# attiny84_bo.net
KiCad netlist of a schematic drawn in EAGLE
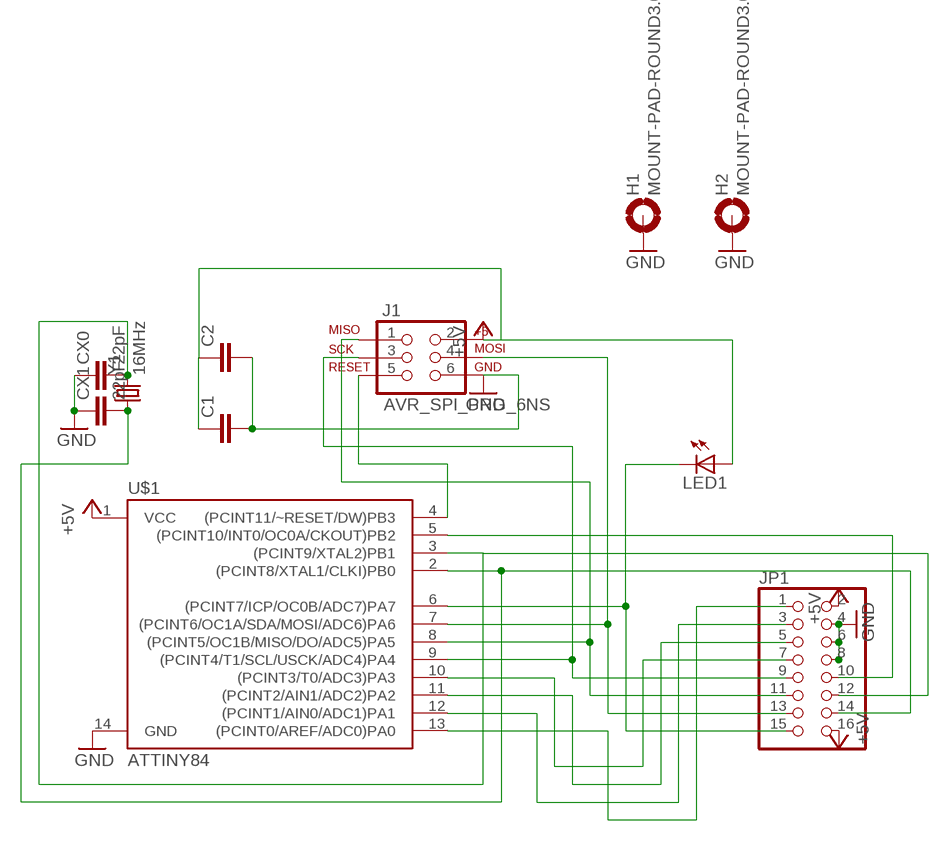
[diagram p0: schematic, sheet 1]

(export (version "E")
  (design (tool "Eeschema 10.0.6"))
  (components
    (comp (ref "C1")
      (value "C-EUC0805")
      (footprint "eagle-import:C0805")
      (libsource (lib "eagle-import") (part "C-EUC0805"))
    )
    (comp (ref "C2")
      (value "C-EUC0805")
      (footprint "eagle-import:C0805")
      (libsource (lib "eagle-import") (part "C-EUC0805"))
    )
    (comp (ref "CX0")
      (value "22pF")
      (footprint "eagle-import:C0603")
      (libsource (lib "eagle-import") (part "C-EUC0603"))
    )
    (comp (ref "CX1")
      (value "22pF")
      (footprint "eagle-import:C0603")
      (libsource (lib "eagle-import") (part "C-EUC0603"))
    )
    (comp (ref "H1")
      (value "MOUNT-PAD-ROUND3.0")
      (footprint "eagle-import:3,0-PAD")
      (libsource (lib "eagle-import") (part "MOUNT-PAD-ROUND3.0"))
    )
    (comp (ref "H2")
      (value "MOUNT-PAD-ROUND3.0")
      (footprint "eagle-import:3,0-PAD")
      (libsource (lib "eagle-import") (part "MOUNT-PAD-ROUND3.0"))
    )
    (comp (ref "J1")
      (value "AVR_SPI_PRG_6NS")
      (footprint "eagle-import:2X3-NS")
      (libsource (lib "eagle-import") (part "AVR_SPI_PRG_6NS"))
    )
    (comp (ref "JP1")
      (value "PINHD-2X8")
      (footprint "eagle-import:2X08")
      (libsource (lib "eagle-import") (part "PINHD-2X8"))
    )
    (comp (ref "LED1")
      (value "LED0603")
      (footprint "eagle-import:LED-0603")
      (libsource (lib "eagle-import") (part "LED0603"))
    )
    (comp (ref "U$1")
      (value "ATTINY84")
      (footprint "eagle-import:SO14")
      (libsource (lib "eagle-import") (part "ATTINY84"))
    )
    (comp (ref "Y1")
      (value "16MHz")
      (footprint "eagle-import:CRYSTAL-SMD-5X3")
      (libsource (lib "eagle-import") (part "CRYSTAL5X3"))
    )
  )
  (nets
    (net (code "1") (name "+5V") (class "Default")
      (node (ref "C1") (pin "1") (pinfunction "1_1") (pintype "passive"))
      (node (ref "C2") (pin "1") (pinfunction "1_1") (pintype "passive"))
      (node (ref "J1") (pin "2") (pinfunction "2_2") (pintype "passive"))
      (node (ref "JP1") (pin "16") (pinfunction "16_16") (pintype "passive"))
      (node (ref "JP1") (pin "2") (pinfunction "2_2") (pintype "passive"))
      (node (ref "LED1") (pin "A") (pinfunction "A_A") (pintype "passive"))
      (node (ref "U$1") (pin "1") (pinfunction "VCC_1") (pintype "bidirectional"))
    )
    (net (code "2") (name "GND") (class "Default")
      (node (ref "C1") (pin "2") (pinfunction "2_2") (pintype "passive"))
      (node (ref "C2") (pin "2") (pinfunction "2_2") (pintype "passive"))
      (node (ref "CX0") (pin "1") (pinfunction "1_1") (pintype "passive"))
      (node (ref "CX1") (pin "1") (pinfunction "1_1") (pintype "passive"))
      (node (ref "H1") (pin "B3,0") (pinfunction "MOUNT_B3,0") (pintype "passive"))
      (node (ref "H2") (pin "B3,0") (pinfunction "MOUNT_B3,0") (pintype "passive"))
      (node (ref "J1") (pin "6") (pinfunction "6_6") (pintype "passive"))
      (node (ref "JP1") (pin "4") (pinfunction "4_4") (pintype "passive"))
      (node (ref "JP1") (pin "6") (pinfunction "6_6") (pintype "passive"))
      (node (ref "JP1") (pin "8") (pinfunction "8_8") (pintype "passive"))
      (node (ref "U$1") (pin "14") (pinfunction "GND_14") (pintype "bidirectional"))
    )
    (net (code "3") (name "Net-(U$1-(PCINT0{slash}AREF{slash}ADC0)PA0)") (class "Default")
      (node (ref "JP1") (pin "1") (pinfunction "1_1") (pintype "passive"))
      (node (ref "U$1") (pin "13") (pinfunction "(PCINT0/AREF/ADC0)PA0_13") (pintype "bidirectional"))
    )
    (net (code "4") (name "Net-(U$1-(PCINT1{slash}AIN0{slash}ADC1)PA1)") (class "Default")
      (node (ref "JP1") (pin "3") (pinfunction "3_3") (pintype "passive"))
      (node (ref "U$1") (pin "12") (pinfunction "(PCINT1/AIN0/ADC1)PA1_12") (pintype "bidirectional"))
    )
    (net (code "5") (name "Net-(U$1-(PCINT2{slash}AIN1{slash}ADC2)PA2)") (class "Default")
      (node (ref "JP1") (pin "5") (pinfunction "5_5") (pintype "passive"))
      (node (ref "U$1") (pin "11") (pinfunction "(PCINT2/AIN1/ADC2)PA2_11") (pintype "bidirectional"))
    )
    (net (code "6") (name "Net-(U$1-(PCINT3{slash}T0{slash}ADC3)PA3)") (class "Default")
      (node (ref "JP1") (pin "7") (pinfunction "7_7") (pintype "passive"))
      (node (ref "U$1") (pin "10") (pinfunction "(PCINT3/T0/ADC3)PA3_10") (pintype "bidirectional"))
    )
    (net (code "7") (name "Net-(U$1-(PCINT4{slash}T1{slash}SCL{slash}USCK{slash}ADC4)PA4)") (class "Default")
      (node (ref "J1") (pin "3") (pinfunction "3_3") (pintype "passive"))
      (node (ref "JP1") (pin "9") (pinfunction "9_9") (pintype "passive"))
      (node (ref "U$1") (pin "9") (pinfunction "(PCINT4/T1/SCL/USCK/ADC4)PA4_9") (pintype "bidirectional"))
    )
    (net (code "8") (name "Net-(U$1-(PCINT5{slash}OC1B{slash}MISO{slash}DO{slash}ADC5)PA5)") (class "Default")
      (node (ref "J1") (pin "1") (pinfunction "1_1") (pintype "passive"))
      (node (ref "JP1") (pin "11") (pinfunction "11_11") (pintype "passive"))
      (node (ref "U$1") (pin "8") (pinfunction "(PCINT5/OC1B/MISO/DO/ADC5)PA5_8") (pintype "bidirectional"))
    )
    (net (code "9") (name "Net-(U$1-(PCINT6{slash}OC1A{slash}SDA{slash}MOSI{slash}ADC6)PA6)") (class "Default")
      (node (ref "J1") (pin "4") (pinfunction "4_4") (pintype "passive"))
      (node (ref "JP1") (pin "13") (pinfunction "13_13") (pintype "passive"))
      (node (ref "U$1") (pin "7") (pinfunction "(PCINT6/OC1A/SDA/MOSI/ADC6)PA6_7") (pintype "bidirectional"))
    )
    (net (code "10") (name "Net-(U$1-(PCINT7{slash}ICP{slash}OC0B{slash}ADC7)PA7)") (class "Default")
      (node (ref "JP1") (pin "15") (pinfunction "15_15") (pintype "passive"))
      (node (ref "LED1") (pin "C") (pinfunction "C_C") (pintype "passive"))
      (node (ref "U$1") (pin "6") (pinfunction "(PCINT7/ICP/OC0B/ADC7)PA7_6") (pintype "bidirectional"))
    )
    (net (code "11") (name "Net-(U$1-(PCINT8{slash}XTAL1{slash}CLKI)PB0)") (class "Default")
      (node (ref "CX1") (pin "2") (pinfunction "2_2") (pintype "passive"))
      (node (ref "JP1") (pin "14") (pinfunction "14_14") (pintype "passive"))
      (node (ref "U$1") (pin "2") (pinfunction "(PCINT8/XTAL1/CLKI)PB0_2") (pintype "bidirectional"))
      (node (ref "Y1") (pin "1") (pinfunction "1_1") (pintype "passive"))
    )
    (net (code "12") (name "Net-(U$1-(PCINT9{slash}XTAL2)PB1)") (class "Default")
      (node (ref "CX0") (pin "2") (pinfunction "2_2") (pintype "passive"))
      (node (ref "JP1") (pin "12") (pinfunction "12_12") (pintype "passive"))
      (node (ref "U$1") (pin "3") (pinfunction "(PCINT9/XTAL2)PB1_3") (pintype "bidirectional"))
      (node (ref "Y1") (pin "3") (pinfunction "2_3") (pintype "passive"))
    )
    (net (code "13") (name "Net-(U$1-(PCINT10{slash}INT0{slash}OC0A{slash}CKOUT)PB2)") (class "Default")
      (node (ref "JP1") (pin "10") (pinfunction "10_10") (pintype "passive"))
      (node (ref "U$1") (pin "5") (pinfunction "(PCINT10/INT0/OC0A/CKOUT)PB2_5") (pintype "bidirectional"))
    )
    (net (code "14") (name "Net-(U$1-(PCINT11{slash}~{RESET{slash}DW})PB3)") (class "Default")
      (node (ref "J1") (pin "5") (pinfunction "5_5") (pintype "passive"))
      (node (ref "U$1") (pin "4") (pinfunction "(PCINT11/~{RESET/DW})PB3_4") (pintype "bidirectional"))
    )
  )
)
